# Clock.net
KiCad netlist of a schematic drawn in EasyEDA Pro
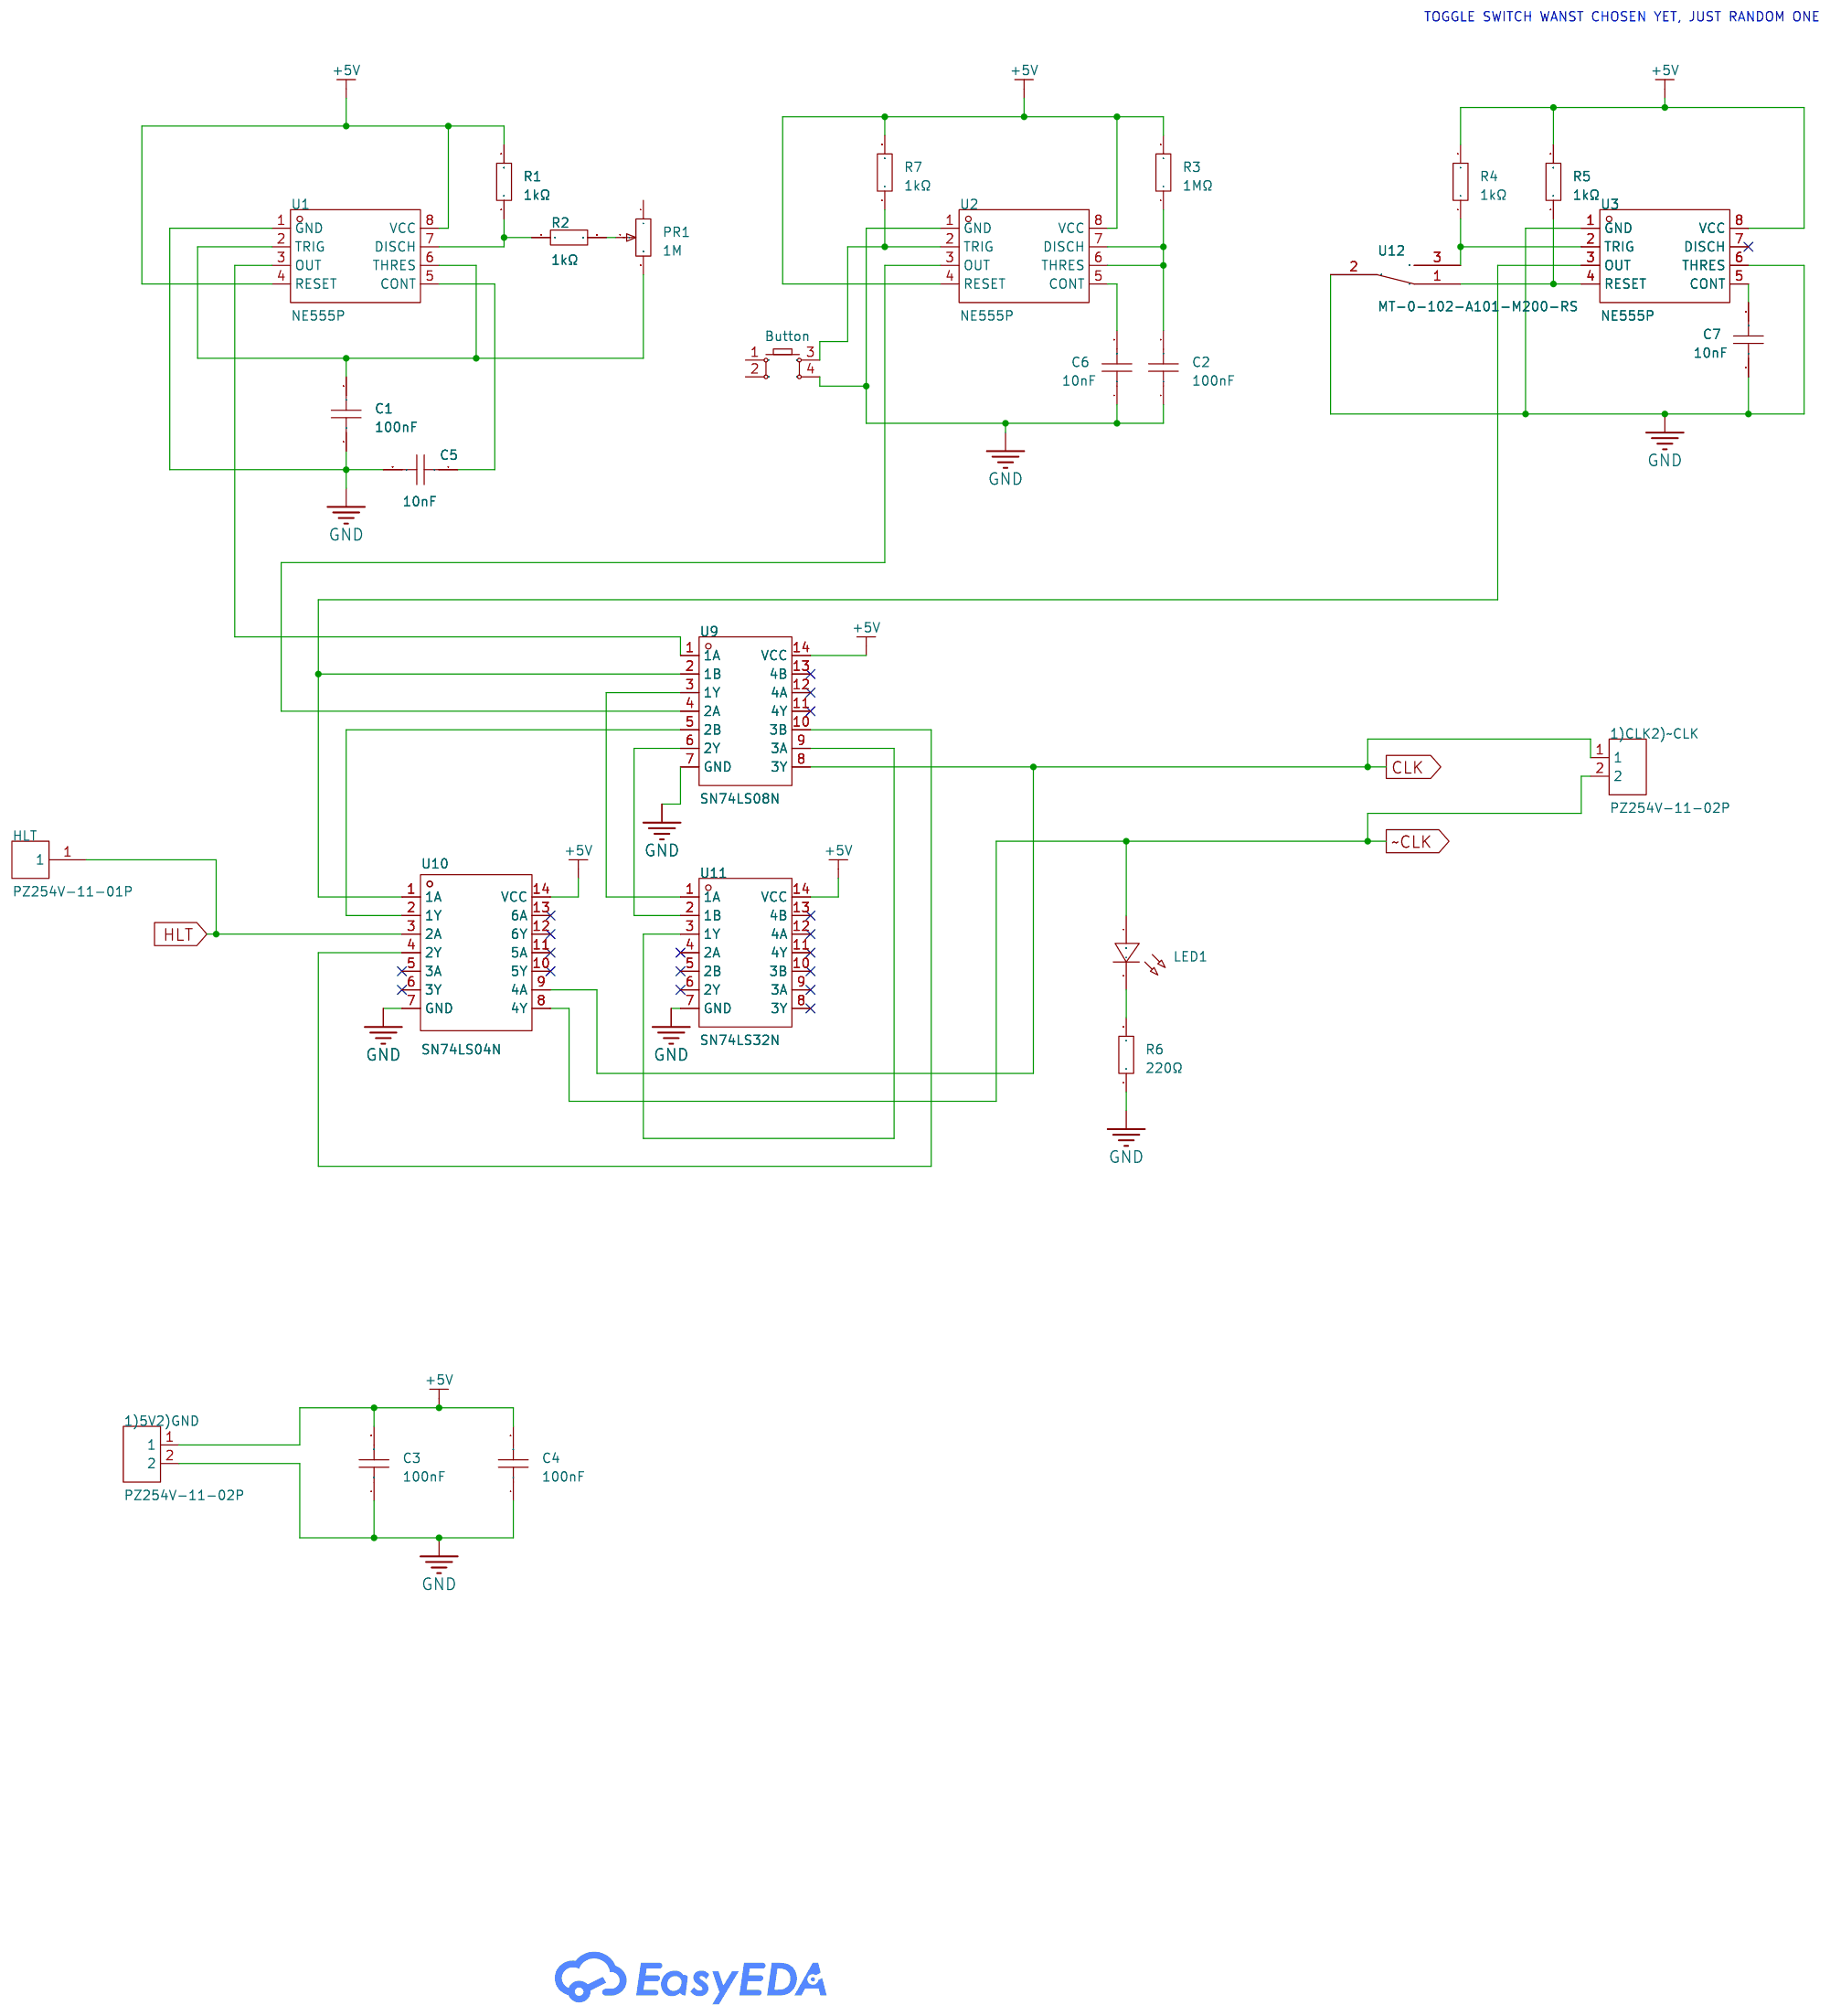
[diagram p0: schematic sheet]

(export (version "E")
  (design (tool "Eeschema 10.0.6"))
  (components
    (comp (ref "1)5V2)GND")
      (value "PZ254V-11-02P")
      (footprint "easyedapro:HDR-TH_2P-P2.54-V-M")
      (fields (field (name "Manufacturer") "XFCN(兴飞)"))
      (libsource (lib "easyedapro") (part "PZ254V-11-02P"))
    )
    (comp (ref "1)CLK2)~CLK")
      (value "PZ254V-11-02P")
      (footprint "easyedapro:HDR-TH_2P-P2.54-V-M")
      (fields (field (name "Manufacturer") "XFCN(兴飞)"))
      (libsource (lib "easyedapro") (part "PZ254V-11-02P"))
    )
    (comp (ref "Button")
      (value "~")
      (footprint "easyedapro:SW-SMD_4P-L6.0-W6.0-P4.50-LS9.0-2")
      (libsource (lib "easyedapro") (part "轻触按键"))
    )
    (comp (ref "C1")
      (value "100nF")
      (footprint "easyedapro:CAP-TH_L8.5-W5.0-P5.00-D1.2")
      (fields (field (name "Manufacturer Part") "CT4-0805B104K500F3") (field (name "Manufacturer") "FH(风华)"))
      (libsource (lib "easyedapro") (part "CT4-0805B104K500F3"))
    )
    (comp (ref "C2")
      (value "100nF")
      (footprint "easyedapro:CAP-TH_L8.5-W5.0-P5.00-D1.2")
      (fields (field (name "Manufacturer Part") "CT4-0805B104K500F3") (field (name "Manufacturer") "FH(风华)"))
      (libsource (lib "easyedapro") (part "CT4-0805B104K500F3"))
    )
    (comp (ref "C3")
      (value "100nF")
      (footprint "easyedapro:CAP-TH_L8.5-W5.0-P5.00-D1.2")
      (fields (field (name "Manufacturer Part") "CT4-0805B104K500F3") (field (name "Manufacturer") "FH(风华)"))
      (libsource (lib "easyedapro") (part "CT4-0805B104K500F3"))
    )
    (comp (ref "C4")
      (value "100nF")
      (footprint "easyedapro:CAP-TH_L8.5-W5.0-P5.00-D1.2")
      (fields (field (name "Manufacturer Part") "CT4-0805B104K500F3") (field (name "Manufacturer") "FH(风华)"))
      (libsource (lib "easyedapro") (part "CT4-0805B104K500F3"))
    )
    (comp (ref "C5")
      (value "10nF")
      (footprint "easyedapro:CAP-TH_L8.5-W5.0-P5.00-D1.2")
      (fields (field (name "Manufacturer Part") "CT4-0805B104K500F3") (field (name "Manufacturer") "FH(风华)"))
      (libsource (lib "easyedapro") (part "CT4-0805B104K500F3"))
    )
    (comp (ref "C6")
      (value "10nF")
      (footprint "easyedapro:CAP-TH_L8.5-W5.0-P5.00-D1.2")
      (fields (field (name "Manufacturer Part") "CT4-0805B104K500F3") (field (name "Manufacturer") "FH(风华)"))
      (libsource (lib "easyedapro") (part "CT4-0805B104K500F3"))
    )
    (comp (ref "C7")
      (value "10nF")
      (footprint "easyedapro:CAP-TH_L8.5-W5.0-P5.00-D1.2")
      (fields (field (name "Manufacturer Part") "CT4-0805B104K500F3") (field (name "Manufacturer") "FH(风华)"))
      (libsource (lib "easyedapro") (part "CT4-0805B104K500F3"))
    )
    (comp (ref "HLT")
      (value "PZ254V-11-01P")
      (footprint "easyedapro:HDR-TH_1P-P2.54-V-M")
      (fields (field (name "Manufacturer") "XFCN(兴飞)"))
      (libsource (lib "easyedapro") (part "PZ254V-11-01P"))
    )
    (comp (ref "LED1")
      (value "~")
      (footprint "easyedapro:LED-TH_BD5.0-P2.54-L-RD_WHITE")
      (libsource (lib "easyedapro") (part "LED_TH-B"))
    )
    (comp (ref "PR1")
      (value "1M")
      (footprint "easyedapro:RES-ADJ-TH_3P-L9.5-W9.5-P2.54-BR-BS")
      (libsource (lib "easyedapro") (part "3386P-1-103LF"))
    )
    (comp (ref "R1")
      (value "1kΩ")
      (footprint "easyedapro:R_AXIAL-0.4")
      (libsource (lib "easyedapro") (part "Res"))
    )
    (comp (ref "R2")
      (value "1kΩ")
      (footprint "easyedapro:R_AXIAL-0.4")
      (libsource (lib "easyedapro") (part "Res"))
    )
    (comp (ref "R3")
      (value "1MΩ")
      (footprint "easyedapro:R_AXIAL-0.4")
      (libsource (lib "easyedapro") (part "Res"))
    )
    (comp (ref "R4")
      (value "1kΩ")
      (footprint "easyedapro:R_AXIAL-0.4")
      (libsource (lib "easyedapro") (part "Res"))
    )
    (comp (ref "R5")
      (value "1kΩ")
      (footprint "easyedapro:R_AXIAL-0.4")
      (libsource (lib "easyedapro") (part "Res"))
    )
    (comp (ref "R6")
      (value "220Ω")
      (footprint "easyedapro:R_AXIAL-0.4")
      (libsource (lib "easyedapro") (part "Res"))
    )
    (comp (ref "R7")
      (value "1kΩ")
      (footprint "easyedapro:R_AXIAL-0.4")
      (libsource (lib "easyedapro") (part "Res"))
    )
    (comp (ref "U1")
      (value "NE555P")
      (footprint "easyedapro:DIP-8_L9.8-W6.6-P2.54-LS7.6-BL")
      (fields (field (name "Manufacturer") "TI(德州仪器)"))
      (libsource (lib "easyedapro") (part "NE555P"))
    )
    (comp (ref "U2")
      (value "NE555P")
      (footprint "easyedapro:DIP-8_L9.8-W6.6-P2.54-LS7.6-BL")
      (fields (field (name "Manufacturer") "TI(德州仪器)"))
      (libsource (lib "easyedapro") (part "NE555P"))
    )
    (comp (ref "U3")
      (value "NE555P")
      (footprint "easyedapro:DIP-8_L9.8-W6.6-P2.54-LS7.6-BL")
      (fields (field (name "Manufacturer") "TI(德州仪器)"))
      (libsource (lib "easyedapro") (part "NE555P"))
    )
    (comp (ref "U9")
      (value "SN74LS08N")
      (footprint "easyedapro:PDIP-14_L19.3-W6.4-P2.54-LS7.9-BL-1")
      (fields (field (name "Manufacturer") "TI(德州仪器)"))
      (libsource (lib "easyedapro") (part "SN74LS08N"))
    )
    (comp (ref "U10")
      (value "SN74LS04N")
      (footprint "easyedapro:PDIP-14_L19.7-W6.6-P2.54-LS8.3-BL")
      (fields (field (name "Manufacturer") "TI(德州仪器)"))
      (libsource (lib "easyedapro") (part "SN74LS04N"))
    )
    (comp (ref "U11")
      (value "SN74LS32N")
      (footprint "easyedapro:PDIP-14_L19.6-W6.5-P2.54-LS7.9-BL")
      (fields (field (name "Manufacturer") "TI(德州仪器)"))
      (libsource (lib "easyedapro") (part "SN74LS32N"))
    )
    (comp (ref "U12")
      (value "MT-0-102-A101-M200-RS")
      (footprint "easyedapro:SW-TH_MT-0-103-A101-M200-RS")
      (fields (field (name "Manufacturer") "YUEN FUNG(源丰)"))
      (libsource (lib "easyedapro") (part "MT-0-102-A101-M200-RS+PJ"))
    )
  )
  (nets
    (net (code "1") (name "+5V") (class "Default")
      (node (ref "1)5V2)GND") (pin "1") (pinfunction "1_1") (pintype "unspecified"))
      (node (ref "C3") (pin "2") (pinfunction "2_2") (pintype "unspecified"))
      (node (ref "C4") (pin "2") (pinfunction "2_2") (pintype "unspecified"))
      (node (ref "R1") (pin "2") (pinfunction "2_2") (pintype "input"))
      (node (ref "R3") (pin "2") (pinfunction "2_2") (pintype "input"))
      (node (ref "R4") (pin "2") (pinfunction "2_2") (pintype "input"))
      (node (ref "R5") (pin "2") (pinfunction "2_2") (pintype "input"))
      (node (ref "R7") (pin "2") (pinfunction "2_2") (pintype "input"))
      (node (ref "U1") (pin "4") (pinfunction "RESET_4") (pintype "input"))
      (node (ref "U1") (pin "8") (pinfunction "VCC_8") (pintype "input"))
      (node (ref "U10") (pin "14") (pinfunction "VCC_14") (pintype "unspecified"))
      (node (ref "U11") (pin "14") (pinfunction "VCC_14") (pintype "input"))
      (node (ref "U2") (pin "4") (pinfunction "RESET_4") (pintype "input"))
      (node (ref "U2") (pin "8") (pinfunction "VCC_8") (pintype "input"))
      (node (ref "U3") (pin "8") (pinfunction "VCC_8") (pintype "input"))
      (node (ref "U9") (pin "14") (pinfunction "VCC_14") (pintype "unspecified"))
    )
    (net (code "2") (name "CLK") (class "Default")
      (node (ref "1)CLK2)~CLK") (pin "1") (pinfunction "1_1") (pintype "unspecified"))
      (node (ref "U10") (pin "9") (pinfunction "4A_9") (pintype "unspecified"))
      (node (ref "U9") (pin "8") (pinfunction "3Y_8") (pintype "unspecified"))
    )
    (net (code "3") (name "GND") (class "Default")
      (node (ref "1)5V2)GND") (pin "2") (pinfunction "2_2") (pintype "unspecified"))
      (node (ref "Button") (pin "4") (pinfunction "4_4") (pintype "input"))
      (node (ref "C1") (pin "1") (pinfunction "1_1") (pintype "unspecified"))
      (node (ref "C2") (pin "1") (pinfunction "1_1") (pintype "unspecified"))
      (node (ref "C3") (pin "1") (pinfunction "1_1") (pintype "unspecified"))
      (node (ref "C4") (pin "1") (pinfunction "1_1") (pintype "unspecified"))
      (node (ref "C5") (pin "2") (pinfunction "2_2") (pintype "unspecified"))
      (node (ref "C6") (pin "1") (pinfunction "1_1") (pintype "unspecified"))
      (node (ref "C7") (pin "1") (pinfunction "1_1") (pintype "unspecified"))
      (node (ref "R6") (pin "1") (pinfunction "1_1") (pintype "input"))
      (node (ref "U1") (pin "1") (pinfunction "GND_1") (pintype "input"))
      (node (ref "U10") (pin "7") (pinfunction "GND_7") (pintype "unspecified"))
      (node (ref "U11") (pin "7") (pinfunction "GND_7") (pintype "input"))
      (node (ref "U12") (pin "2") (pinfunction "2_2") (pintype "unspecified"))
      (node (ref "U2") (pin "1") (pinfunction "GND_1") (pintype "input"))
      (node (ref "U3") (pin "1") (pinfunction "GND_1") (pintype "input"))
      (node (ref "U3") (pin "6") (pinfunction "THRES_6") (pintype "input"))
      (node (ref "U9") (pin "7") (pinfunction "GND_7") (pintype "unspecified"))
    )
    (net (code "4") (name "HLT") (class "Default")
      (node (ref "HLT") (pin "1") (pinfunction "1_1") (pintype "unspecified"))
      (node (ref "U10") (pin "3") (pinfunction "2A_3") (pintype "unspecified"))
    )
    (net (code "5") (name "Net-(LED1-A)") (class "Default")
      (node (ref "LED1") (pin "2") (pinfunction "A_2") (pintype "input"))
      (node (ref "R6") (pin "2") (pinfunction "2_2") (pintype "input"))
    )
    (net (code "6") (name "Net-(PR1-Pad2)") (class "Default")
      (node (ref "PR1") (pin "2") (pinfunction "2_2") (pintype "input"))
      (node (ref "R2") (pin "2") (pinfunction "2_2") (pintype "input"))
    )
    (net (code "7") (name "Net-(U1-CONT)") (class "Default")
      (node (ref "C5") (pin "1") (pinfunction "1_1") (pintype "unspecified"))
      (node (ref "U1") (pin "5") (pinfunction "CONT_5") (pintype "input"))
    )
    (net (code "8") (name "Net-(U1-DISCH)") (class "Default")
      (node (ref "R1") (pin "1") (pinfunction "1_1") (pintype "input"))
      (node (ref "R2") (pin "1") (pinfunction "1_1") (pintype "input"))
      (node (ref "U1") (pin "7") (pinfunction "DISCH_7") (pintype "input"))
    )
    (net (code "9") (name "Net-(U1-OUT)") (class "Default")
      (node (ref "U1") (pin "3") (pinfunction "OUT_3") (pintype "input"))
      (node (ref "U9") (pin "1") (pinfunction "1A_1") (pintype "unspecified"))
    )
    (net (code "10") (name "Net-(U1-THRES)") (class "Default")
      (node (ref "C1") (pin "2") (pinfunction "2_2") (pintype "unspecified"))
      (node (ref "PR1") (pin "3") (pinfunction "3_3") (pintype "input"))
      (node (ref "U1") (pin "2") (pinfunction "TRIG_2") (pintype "input"))
      (node (ref "U1") (pin "6") (pinfunction "THRES_6") (pintype "input"))
    )
    (net (code "11") (name "Net-(U2-CONT)") (class "Default")
      (node (ref "C6") (pin "2") (pinfunction "2_2") (pintype "unspecified"))
      (node (ref "U2") (pin "5") (pinfunction "CONT_5") (pintype "input"))
    )
    (net (code "12") (name "Net-(U2-DISCH)") (class "Default")
      (node (ref "C2") (pin "2") (pinfunction "2_2") (pintype "unspecified"))
      (node (ref "R3") (pin "1") (pinfunction "1_1") (pintype "input"))
      (node (ref "U2") (pin "6") (pinfunction "THRES_6") (pintype "input"))
      (node (ref "U2") (pin "7") (pinfunction "DISCH_7") (pintype "input"))
    )
    (net (code "13") (name "Net-(U2-OUT)") (class "Default")
      (node (ref "U2") (pin "3") (pinfunction "OUT_3") (pintype "input"))
      (node (ref "U9") (pin "4") (pinfunction "2A_4") (pintype "unspecified"))
    )
    (net (code "14") (name "Net-(U2-TRIG)") (class "Default")
      (node (ref "Button") (pin "3") (pinfunction "3_3") (pintype "input"))
      (node (ref "R7") (pin "1") (pinfunction "1_1") (pintype "input"))
      (node (ref "U2") (pin "2") (pinfunction "TRIG_2") (pintype "input"))
    )
    (net (code "15") (name "Net-(U3-CONT)") (class "Default")
      (node (ref "C7") (pin "2") (pinfunction "2_2") (pintype "unspecified"))
      (node (ref "U3") (pin "5") (pinfunction "CONT_5") (pintype "input"))
    )
    (net (code "16") (name "Net-(U3-RESET)") (class "Default")
      (node (ref "R5") (pin "1") (pinfunction "1_1") (pintype "input"))
      (node (ref "U12") (pin "1") (pinfunction "1_1") (pintype "unspecified"))
      (node (ref "U3") (pin "4") (pinfunction "RESET_4") (pintype "input"))
    )
    (net (code "17") (name "Net-(U3-TRIG)") (class "Default")
      (node (ref "R4") (pin "1") (pinfunction "1_1") (pintype "input"))
      (node (ref "U12") (pin "3") (pinfunction "3_3") (pintype "unspecified"))
      (node (ref "U3") (pin "2") (pinfunction "TRIG_2") (pintype "input"))
    )
    (net (code "18") (name "Net-(U10-1A)") (class "Default")
      (node (ref "U10") (pin "1") (pinfunction "1A_1") (pintype "unspecified"))
      (node (ref "U3") (pin "3") (pinfunction "OUT_3") (pintype "input"))
      (node (ref "U9") (pin "2") (pinfunction "1B_2") (pintype "unspecified"))
    )
    (net (code "19") (name "Net-(U10-1Y)") (class "Default")
      (node (ref "U10") (pin "2") (pinfunction "1Y_2") (pintype "unspecified"))
      (node (ref "U9") (pin "5") (pinfunction "2B_5") (pintype "unspecified"))
    )
    (net (code "20") (name "Net-(U10-2Y)") (class "Default")
      (node (ref "U10") (pin "4") (pinfunction "2Y_4") (pintype "unspecified"))
      (node (ref "U9") (pin "10") (pinfunction "3B_10") (pintype "unspecified"))
    )
    (net (code "21") (name "Net-(U11-1A)") (class "Default")
      (node (ref "U11") (pin "1") (pinfunction "1A_1") (pintype "input"))
      (node (ref "U9") (pin "3") (pinfunction "1Y_3") (pintype "unspecified"))
    )
    (net (code "22") (name "Net-(U11-1B)") (class "Default")
      (node (ref "U11") (pin "2") (pinfunction "1B_2") (pintype "input"))
      (node (ref "U9") (pin "6") (pinfunction "2Y_6") (pintype "unspecified"))
    )
    (net (code "23") (name "Net-(U11-1Y)") (class "Default")
      (node (ref "U11") (pin "3") (pinfunction "1Y_3") (pintype "input"))
      (node (ref "U9") (pin "9") (pinfunction "3A_9") (pintype "unspecified"))
    )
    (net (code "24") (name "unconnected-(Button-Pad1)") (class "Default")
      (node (ref "Button") (pin "1") (pinfunction "1_1") (pintype "input"))
    )
    (net (code "25") (name "unconnected-(Button-Pad2)") (class "Default")
      (node (ref "Button") (pin "2") (pinfunction "2_2") (pintype "input"))
    )
    (net (code "26") (name "unconnected-(PR1-Pad1)") (class "Default")
      (node (ref "PR1") (pin "1") (pinfunction "1_1") (pintype "input"))
    )
    (net (code "27") (name "unconnected-(U3-DISCH-Pad7)") (class "Default")
      (node (ref "U3") (pin "7") (pinfunction "DISCH_7") (pintype "input+no_connect"))
    )
    (net (code "28") (name "unconnected-(U9-4A-Pad12)") (class "Default")
      (node (ref "U9") (pin "12") (pinfunction "4A_12") (pintype "unspecified+no_connect"))
    )
    (net (code "29") (name "unconnected-(U9-4B-Pad13)") (class "Default")
      (node (ref "U9") (pin "13") (pinfunction "4B_13") (pintype "unspecified+no_connect"))
    )
    (net (code "30") (name "unconnected-(U9-4Y-Pad11)") (class "Default")
      (node (ref "U9") (pin "11") (pinfunction "4Y_11") (pintype "unspecified+no_connect"))
    )
    (net (code "31") (name "unconnected-(U10-3A-Pad5)") (class "Default")
      (node (ref "U10") (pin "5") (pinfunction "3A_5") (pintype "unspecified+no_connect"))
    )
    (net (code "32") (name "unconnected-(U10-3Y-Pad6)") (class "Default")
      (node (ref "U10") (pin "6") (pinfunction "3Y_6") (pintype "unspecified+no_connect"))
    )
    (net (code "33") (name "unconnected-(U10-5A-Pad11)") (class "Default")
      (node (ref "U10") (pin "11") (pinfunction "5A_11") (pintype "unspecified+no_connect"))
    )
    (net (code "34") (name "unconnected-(U10-5Y-Pad10)") (class "Default")
      (node (ref "U10") (pin "10") (pinfunction "5Y_10") (pintype "unspecified+no_connect"))
    )
    (net (code "35") (name "unconnected-(U10-6A-Pad13)") (class "Default")
      (node (ref "U10") (pin "13") (pinfunction "6A_13") (pintype "unspecified+no_connect"))
    )
    (net (code "36") (name "unconnected-(U10-6Y-Pad12)") (class "Default")
      (node (ref "U10") (pin "12") (pinfunction "6Y_12") (pintype "unspecified+no_connect"))
    )
    (net (code "37") (name "unconnected-(U11-2A-Pad4)") (class "Default")
      (node (ref "U11") (pin "4") (pinfunction "2A_4") (pintype "input+no_connect"))
    )
    (net (code "38") (name "unconnected-(U11-2B-Pad5)") (class "Default")
      (node (ref "U11") (pin "5") (pinfunction "2B_5") (pintype "input+no_connect"))
    )
    (net (code "39") (name "unconnected-(U11-2Y-Pad6)") (class "Default")
      (node (ref "U11") (pin "6") (pinfunction "2Y_6") (pintype "input+no_connect"))
    )
    (net (code "40") (name "unconnected-(U11-3A-Pad9)") (class "Default")
      (node (ref "U11") (pin "9") (pinfunction "3A_9") (pintype "input+no_connect"))
    )
    (net (code "41") (name "unconnected-(U11-3B-Pad10)") (class "Default")
      (node (ref "U11") (pin "10") (pinfunction "3B_10") (pintype "input+no_connect"))
    )
    (net (code "42") (name "unconnected-(U11-3Y-Pad8)") (class "Default")
      (node (ref "U11") (pin "8") (pinfunction "3Y_8") (pintype "input+no_connect"))
    )
    (net (code "43") (name "unconnected-(U11-4A-Pad12)") (class "Default")
      (node (ref "U11") (pin "12") (pinfunction "4A_12") (pintype "input+no_connect"))
    )
    (net (code "44") (name "unconnected-(U11-4B-Pad13)") (class "Default")
      (node (ref "U11") (pin "13") (pinfunction "4B_13") (pintype "input+no_connect"))
    )
    (net (code "45") (name "unconnected-(U11-4Y-Pad11)") (class "Default")
      (node (ref "U11") (pin "11") (pinfunction "4Y_11") (pintype "input+no_connect"))
    )
    (net (code "46") (name "~CLK") (class "Default")
      (node (ref "1)CLK2)~CLK") (pin "2") (pinfunction "2_2") (pintype "unspecified"))
      (node (ref "LED1") (pin "1") (pinfunction "C_1") (pintype "input"))
      (node (ref "U10") (pin "8") (pinfunction "4Y_8") (pintype "unspecified"))
    )
  )
)
